# uHexV1_pub.net
KiCad netlist of a schematic drawn in EAGLE
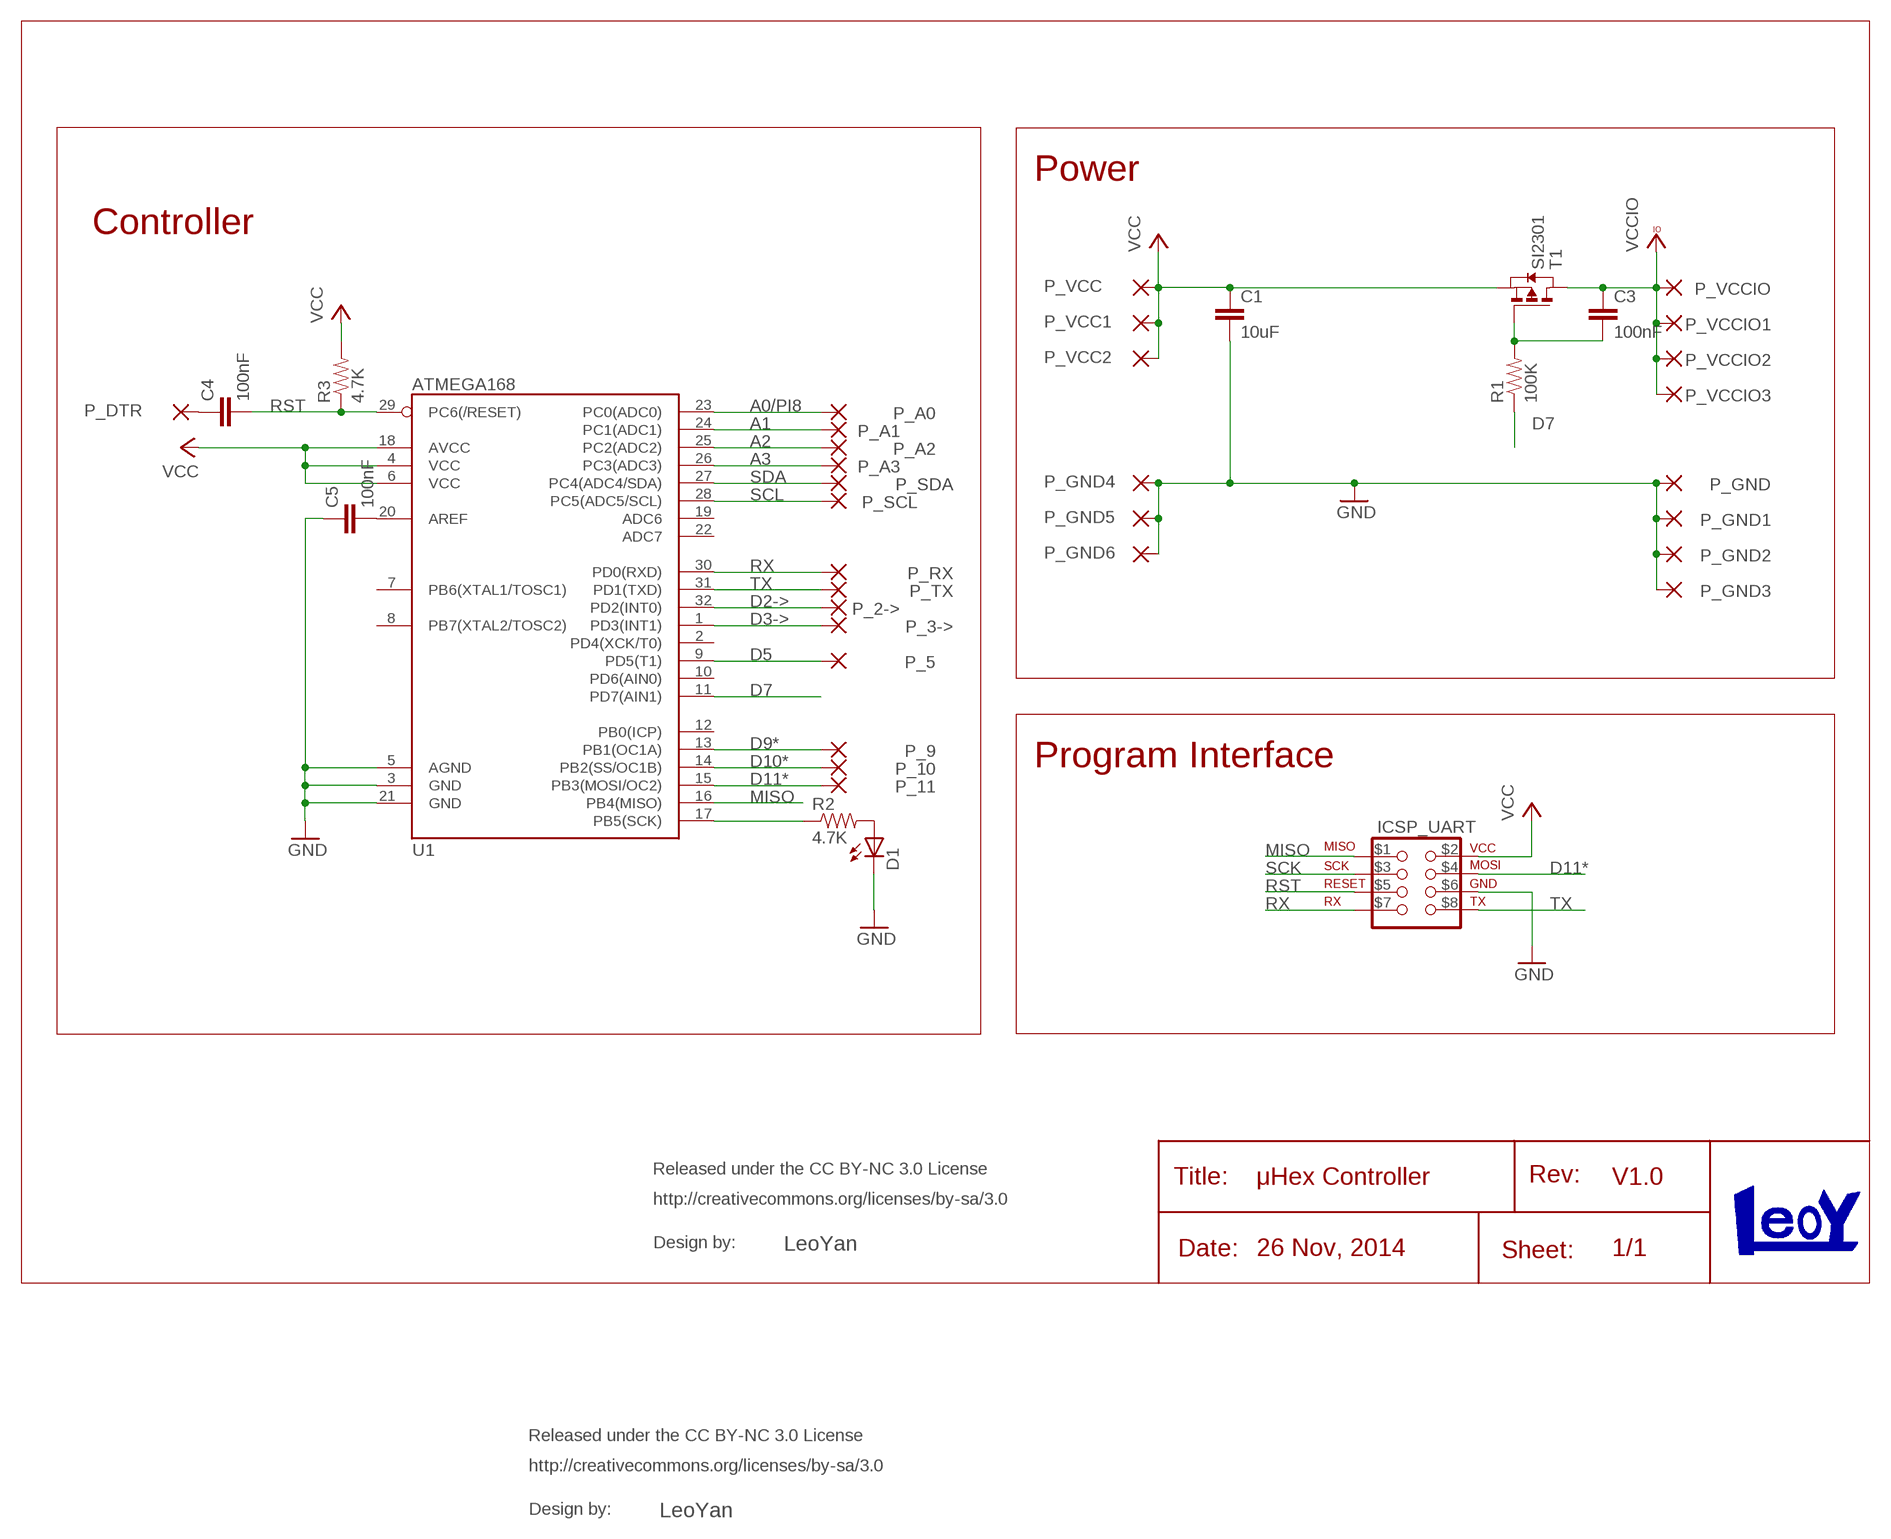
[diagram p0: schematic, sheet 1]

(export (version "E")
  (design (tool "Eeschema 10.0.6"))
  (components
    (comp (ref "C1")
      (value "10uF")
      (footprint "eagle-import:C0603K")
      (libsource (lib "eagle-import") (part "resistor_C-EUC0603K"))
    )
    (comp (ref "C3")
      (value "100nF")
      (footprint "eagle-import:C0603K")
      (libsource (lib "eagle-import") (part "C-EUC0603K"))
    )
    (comp (ref "C4")
      (value "100nF")
      (footprint "eagle-import:C0603K")
      (libsource (lib "eagle-import") (part "C-EUC0603K"))
    )
    (comp (ref "C5")
      (value "100nF")
      (footprint "eagle-import:C0603K")
      (libsource (lib "eagle-import") (part "C-EUC0603K"))
    )
    (comp (ref "D1")
      (value "LED-YELLOW0603")
      (footprint "eagle-import:LED-0603")
      (libsource (lib "eagle-import") (part "LED-YELLOW0603"))
    )
    (comp (ref "ICSP_UART")
      (value "ICSP_UART_CONNICSP_UAST_HOLE")
      (footprint "eagle-import:ICSP_UART_CONN_HOLE")
      (libsource (lib "eagle-import") (part "ICSP_UART_CONNICSP_UAST_HOLE"))
    )
    (comp (ref "P_2->")
      (value "TH-PAD2.54M01_TH_OFFSET")
      (footprint "eagle-import:TH_PAD_OFFSET")
      (libsource (lib "eagle-import") (part "TH-PAD2.54M01_TH_OFFSET"))
    )
    (comp (ref "P_3->")
      (value "TH-PAD2.54M01_TH_OFFSET")
      (footprint "eagle-import:TH_PAD_OFFSET")
      (libsource (lib "eagle-import") (part "TH-PAD2.54M01_TH_OFFSET"))
    )
    (comp (ref "P_5")
      (value "TH-PAD2.54M01_TH_HORN")
      (footprint "eagle-import:TH_PAD_HORN")
      (libsource (lib "eagle-import") (part "TH-PAD2.54M01_TH_HORN"))
    )
    (comp (ref "P_9")
      (value "TH-PAD2.54M01_TH_OFFSET")
      (footprint "eagle-import:TH_PAD_OFFSET")
      (libsource (lib "eagle-import") (part "TH-PAD2.54M01_TH_OFFSET"))
    )
    (comp (ref "P_10")
      (value "TH-PAD2.54M01_TH_OFFSET")
      (footprint "eagle-import:TH_PAD_OFFSET")
      (libsource (lib "eagle-import") (part "TH-PAD2.54M01_TH_OFFSET"))
    )
    (comp (ref "P_11")
      (value "TH-PAD2.54M01_TH_HORN")
      (footprint "eagle-import:TH_PAD_HORN")
      (libsource (lib "eagle-import") (part "TH-PAD2.54M01_TH_HORN"))
    )
    (comp (ref "P_A0")
      (value "TH-PAD2.54M01_TH_HORN")
      (footprint "eagle-import:TH_PAD_HORN")
      (libsource (lib "eagle-import") (part "TH-PAD2.54M01_TH_HORN"))
    )
    (comp (ref "P_A1")
      (value "TH-PAD2.54M01_TH_OFFSET")
      (footprint "eagle-import:TH_PAD_OFFSET")
      (libsource (lib "eagle-import") (part "TH-PAD2.54M01_TH_OFFSET"))
    )
    (comp (ref "P_A2")
      (value "TH-PAD2.54M01_TH_OFFSET")
      (footprint "eagle-import:TH_PAD_OFFSET")
      (libsource (lib "eagle-import") (part "TH-PAD2.54M01_TH_OFFSET"))
    )
    (comp (ref "P_A3")
      (value "TH-PAD2.54M01_TH_HORN")
      (footprint "eagle-import:TH_PAD_HORN")
      (libsource (lib "eagle-import") (part "TH-PAD2.54M01_TH_HORN"))
    )
    (comp (ref "P_DTR")
      (value "TH-PAD2.54MO1_TH_DTR")
      (footprint "eagle-import:TH_PAD_DTR")
      (libsource (lib "eagle-import") (part "TH-PAD2.54MO1_TH_DTR"))
    )
    (comp (ref "P_GND")
      (value "TH-PAD2.54M01_TH_PWR")
      (footprint "eagle-import:TH_PAD_PWR")
      (libsource (lib "eagle-import") (part "TH-PAD2.54M01_TH_PWR"))
    )
    (comp (ref "P_GND1")
      (value "TH-PAD2.54OFFSET")
      (footprint "eagle-import:TH_PAD_PWR_OFFSET")
      (libsource (lib "eagle-import") (part "TH-PAD2.54OFFSET"))
    )
    (comp (ref "P_GND2")
      (value "TH-PAD2.54OFFSET")
      (footprint "eagle-import:TH_PAD_PWR_OFFSET")
      (libsource (lib "eagle-import") (part "TH-PAD2.54OFFSET"))
    )
    (comp (ref "P_GND3")
      (value "TH-PAD2.54OFFSET")
      (footprint "eagle-import:TH_PAD_PWR_OFFSET")
      (libsource (lib "eagle-import") (part "TH-PAD2.54OFFSET"))
    )
    (comp (ref "P_GND4")
      (value "TH-PAD2.54OFFSET")
      (footprint "eagle-import:TH_PAD_PWR_OFFSET")
      (libsource (lib "eagle-import") (part "TH-PAD2.54OFFSET"))
    )
    (comp (ref "P_GND5")
      (value "TH-PAD2.54OFFSET")
      (footprint "eagle-import:TH_PAD_PWR_OFFSET")
      (libsource (lib "eagle-import") (part "TH-PAD2.54OFFSET"))
    )
    (comp (ref "P_GND6")
      (value "TH-PAD2.54OFFSET")
      (footprint "eagle-import:TH_PAD_PWR_OFFSET")
      (libsource (lib "eagle-import") (part "TH-PAD2.54OFFSET"))
    )
    (comp (ref "P_RX")
      (value "TH-PAD2.54M01_TH_OFFSET")
      (footprint "eagle-import:TH_PAD_OFFSET")
      (libsource (lib "eagle-import") (part "TH-PAD2.54M01_TH_OFFSET"))
    )
    (comp (ref "P_SCL")
      (value "TH-PAD2.54M01_TH_OFFSET")
      (footprint "eagle-import:TH_PAD_OFFSET")
      (libsource (lib "eagle-import") (part "TH-PAD2.54M01_TH_OFFSET"))
    )
    (comp (ref "P_SDA")
      (value "TH-PAD2.54M01_TH_OFFSET")
      (footprint "eagle-import:TH_PAD_OFFSET")
      (libsource (lib "eagle-import") (part "TH-PAD2.54M01_TH_OFFSET"))
    )
    (comp (ref "P_TX")
      (value "TH-PAD2.54M01_TH_OFFSET")
      (footprint "eagle-import:TH_PAD_OFFSET")
      (libsource (lib "eagle-import") (part "TH-PAD2.54M01_TH_OFFSET"))
    )
    (comp (ref "P_VCC")
      (value "TH-PAD2.54OFFSET")
      (footprint "eagle-import:TH_PAD_PWR_OFFSET")
      (libsource (lib "eagle-import") (part "TH-PAD2.54OFFSET"))
    )
    (comp (ref "P_VCC1")
      (value "TH-PAD2.54M01_TH_PWR")
      (footprint "eagle-import:TH_PAD_PWR")
      (libsource (lib "eagle-import") (part "TH-PAD2.54M01_TH_PWR"))
    )
    (comp (ref "P_VCC2")
      (value "TH-PAD2.54OFFSET")
      (footprint "eagle-import:TH_PAD_PWR_OFFSET")
      (libsource (lib "eagle-import") (part "TH-PAD2.54OFFSET"))
    )
    (comp (ref "P_VCCIO")
      (value "TH-PAD2.54OFFSET")
      (footprint "eagle-import:TH_PAD_PWR_OFFSET")
      (libsource (lib "eagle-import") (part "TH-PAD2.54OFFSET"))
    )
    (comp (ref "P_VCCIO1")
      (value "TH-PAD2.54OFFSET")
      (footprint "eagle-import:TH_PAD_PWR_OFFSET")
      (libsource (lib "eagle-import") (part "TH-PAD2.54OFFSET"))
    )
    (comp (ref "P_VCCIO2")
      (value "TH-PAD2.54OFFSET")
      (footprint "eagle-import:TH_PAD_PWR_OFFSET")
      (libsource (lib "eagle-import") (part "TH-PAD2.54OFFSET"))
    )
    (comp (ref "P_VCCIO3")
      (value "TH-PAD2.54OFFSET")
      (footprint "eagle-import:TH_PAD_PWR_OFFSET")
      (libsource (lib "eagle-import") (part "TH-PAD2.54OFFSET"))
    )
    (comp (ref "R1")
      (value "100K")
      (footprint "eagle-import:0603-RES")
      (libsource (lib "eagle-import") (part "RESISTOR0603-RES"))
    )
    (comp (ref "R2")
      (value "4.7K")
      (footprint "eagle-import:0603-RES")
      (libsource (lib "eagle-import") (part "RESISTOR0603-RES"))
    )
    (comp (ref "R3")
      (value "4.7K")
      (footprint "eagle-import:0603-RES")
      (libsource (lib "eagle-import") (part "RESISTOR0603-RES"))
    )
    (comp (ref "T1")
      (value "SI2301")
      (footprint "eagle-import:SOT-23")
      (libsource (lib "eagle-import") (part "PMOSSOT23"))
    )
    (comp (ref "U1")
      (value "ATMEGA168")
      (footprint "eagle-import:TQFP32-08")
      (libsource (lib "eagle-import") (part "ATMEGA168"))
    )
  )
  (nets
    (net (code "1") (name "/A0{slash}PI8") (class "Default")
      (node (ref "P_A0") (pin "1") (pinfunction "P$_1") (pintype "bidirectional"))
      (node (ref "U1") (pin "23") (pinfunction "PC0(ADC0)_23") (pintype "bidirectional"))
    )
    (net (code "2") (name "/A1") (class "Default")
      (node (ref "P_A1") (pin "P$1") (pinfunction "P$_P$1") (pintype "bidirectional"))
      (node (ref "U1") (pin "24") (pinfunction "PC1(ADC1)_24") (pintype "bidirectional"))
    )
    (net (code "3") (name "/A2") (class "Default")
      (node (ref "P_A2") (pin "P$1") (pinfunction "P$_P$1") (pintype "bidirectional"))
      (node (ref "U1") (pin "25") (pinfunction "PC2(ADC2)_25") (pintype "bidirectional"))
    )
    (net (code "4") (name "/A3") (class "Default")
      (node (ref "P_A3") (pin "1") (pinfunction "P$_1") (pintype "bidirectional"))
      (node (ref "U1") (pin "26") (pinfunction "PC3(ADC3)_26") (pintype "bidirectional"))
    )
    (net (code "5") (name "/D2->") (class "Default")
      (node (ref "P_2->") (pin "P$1") (pinfunction "P$_P$1") (pintype "bidirectional"))
      (node (ref "U1") (pin "32") (pinfunction "PD2(INT0)_32") (pintype "bidirectional"))
    )
    (net (code "6") (name "/D3->") (class "Default")
      (node (ref "P_3->") (pin "P$1") (pinfunction "P$_P$1") (pintype "bidirectional"))
      (node (ref "U1") (pin "1") (pinfunction "PD3(INT1)_1") (pintype "bidirectional"))
    )
    (net (code "7") (name "/D5") (class "Default")
      (node (ref "P_5") (pin "1") (pinfunction "P$_1") (pintype "bidirectional"))
      (node (ref "U1") (pin "9") (pinfunction "PD5(T1)_9") (pintype "bidirectional"))
    )
    (net (code "8") (name "/D7") (class "Default")
      (node (ref "R1") (pin "1") (pinfunction "1_1") (pintype "passive"))
      (node (ref "U1") (pin "11") (pinfunction "PD7(AIN1)_11") (pintype "bidirectional"))
    )
    (net (code "9") (name "/D9*") (class "Default")
      (node (ref "P_9") (pin "P$1") (pinfunction "P$_P$1") (pintype "bidirectional"))
      (node (ref "U1") (pin "13") (pinfunction "PB1(OC1A)_13") (pintype "bidirectional"))
    )
    (net (code "10") (name "/D10*") (class "Default")
      (node (ref "P_10") (pin "P$1") (pinfunction "P$_P$1") (pintype "bidirectional"))
      (node (ref "U1") (pin "14") (pinfunction "PB2(SS/OC1B)_14") (pintype "bidirectional"))
    )
    (net (code "11") (name "/D11*") (class "Default")
      (node (ref "ICSP_UART") (pin "$4") (pinfunction "4_$4") (pintype "passive"))
      (node (ref "P_11") (pin "1") (pinfunction "P$_1") (pintype "bidirectional"))
      (node (ref "U1") (pin "15") (pinfunction "PB3(MOSI/OC2)_15") (pintype "bidirectional"))
    )
    (net (code "12") (name "/MISO") (class "Default")
      (node (ref "ICSP_UART") (pin "$1") (pinfunction "1_$1") (pintype "output"))
      (node (ref "U1") (pin "16") (pinfunction "PB4(MISO)_16") (pintype "bidirectional"))
    )
    (net (code "13") (name "/RST") (class "Default")
      (node (ref "C4") (pin "2") (pinfunction "2_2") (pintype "passive"))
      (node (ref "ICSP_UART") (pin "$5") (pinfunction "5_$5") (pintype "passive"))
      (node (ref "R3") (pin "1") (pinfunction "1_1") (pintype "passive"))
      (node (ref "U1") (pin "29") (pinfunction "PC6(/RESET)_29") (pintype "bidirectional"))
    )
    (net (code "14") (name "/RX") (class "Default")
      (node (ref "ICSP_UART") (pin "$7") (pinfunction "7_$7") (pintype "passive"))
      (node (ref "P_RX") (pin "P$1") (pinfunction "P$_P$1") (pintype "bidirectional"))
      (node (ref "U1") (pin "30") (pinfunction "PD0(RXD)_30") (pintype "bidirectional"))
    )
    (net (code "15") (name "/SCK") (class "Default")
      (node (ref "ICSP_UART") (pin "$3") (pinfunction "3_$3") (pintype "passive"))
      (node (ref "R2") (pin "1") (pinfunction "1_1") (pintype "passive"))
      (node (ref "U1") (pin "17") (pinfunction "PB5(SCK)_17") (pintype "bidirectional"))
    )
    (net (code "16") (name "/SCL") (class "Default")
      (node (ref "P_SCL") (pin "P$1") (pinfunction "P$_P$1") (pintype "bidirectional"))
      (node (ref "U1") (pin "28") (pinfunction "PC5(ADC5/SCL)_28") (pintype "bidirectional"))
    )
    (net (code "17") (name "/SDA") (class "Default")
      (node (ref "P_SDA") (pin "P$1") (pinfunction "P$_P$1") (pintype "bidirectional"))
      (node (ref "U1") (pin "27") (pinfunction "PC4(ADC4/SDA)_27") (pintype "bidirectional"))
    )
    (net (code "18") (name "/TX") (class "Default")
      (node (ref "ICSP_UART") (pin "$8") (pinfunction "8_$8") (pintype "passive"))
      (node (ref "P_TX") (pin "P$1") (pinfunction "P$_P$1") (pintype "bidirectional"))
      (node (ref "U1") (pin "31") (pinfunction "PD1(TXD)_31") (pintype "bidirectional"))
    )
    (net (code "19") (name "GND") (class "Default")
      (node (ref "C1") (pin "2") (pinfunction "2_2") (pintype "passive"))
      (node (ref "C5") (pin "1") (pinfunction "1_1") (pintype "passive"))
      (node (ref "D1") (pin "C") (pinfunction "C_C") (pintype "passive"))
      (node (ref "ICSP_UART") (pin "$6") (pinfunction "6_$6") (pintype "passive"))
      (node (ref "P_GND") (pin "P$1") (pinfunction "P$_P$1") (pintype "bidirectional"))
      (node (ref "P_GND1") (pin "P$1") (pinfunction "P$_P$1") (pintype "bidirectional"))
      (node (ref "P_GND2") (pin "P$1") (pinfunction "P$_P$1") (pintype "bidirectional"))
      (node (ref "P_GND3") (pin "P$1") (pinfunction "P$_P$1") (pintype "bidirectional"))
      (node (ref "P_GND4") (pin "P$1") (pinfunction "P$_P$1") (pintype "bidirectional"))
      (node (ref "P_GND5") (pin "P$1") (pinfunction "P$_P$1") (pintype "bidirectional"))
      (node (ref "P_GND6") (pin "P$1") (pinfunction "P$_P$1") (pintype "bidirectional"))
      (node (ref "U1") (pin "21") (pinfunction "GND_21") (pintype "bidirectional"))
      (node (ref "U1") (pin "3") (pinfunction "GND_3") (pintype "bidirectional"))
      (node (ref "U1") (pin "5") (pinfunction "AGND_5") (pintype "bidirectional"))
    )
    (net (code "20") (name "Net-(D1-PadA)") (class "Default")
      (node (ref "D1") (pin "A") (pinfunction "A_A") (pintype "passive"))
      (node (ref "R2") (pin "2") (pinfunction "2_2") (pintype "passive"))
    )
    (net (code "21") (name "Net-(P_DTR-P$)") (class "Default")
      (node (ref "C4") (pin "1") (pinfunction "1_1") (pintype "passive"))
      (node (ref "P_DTR") (pin "1") (pinfunction "P$_1") (pintype "bidirectional"))
    )
    (net (code "22") (name "Net-(T1-G)") (class "Default")
      (node (ref "C3") (pin "2") (pinfunction "2_2") (pintype "passive"))
      (node (ref "R1") (pin "2") (pinfunction "2_2") (pintype "passive"))
      (node (ref "T1") (pin "3") (pinfunction "G_3") (pintype "passive"))
    )
    (net (code "23") (name "Net-(U1-AREF)") (class "Default")
      (node (ref "C5") (pin "2") (pinfunction "2_2") (pintype "passive"))
      (node (ref "U1") (pin "20") (pinfunction "AREF_20") (pintype "bidirectional"))
    )
    (net (code "24") (name "VCC") (class "Default")
      (node (ref "C1") (pin "1") (pinfunction "1_1") (pintype "passive"))
      (node (ref "ICSP_UART") (pin "$2") (pinfunction "2_$2") (pintype "power_in"))
      (node (ref "P_VCC") (pin "P$1") (pinfunction "P$_P$1") (pintype "bidirectional"))
      (node (ref "P_VCC1") (pin "P$1") (pinfunction "P$_P$1") (pintype "bidirectional"))
      (node (ref "P_VCC2") (pin "P$1") (pinfunction "P$_P$1") (pintype "bidirectional"))
      (node (ref "R3") (pin "2") (pinfunction "2_2") (pintype "passive"))
      (node (ref "T1") (pin "2") (pinfunction "S_2") (pintype "passive"))
      (node (ref "U1") (pin "18") (pinfunction "AVCC_18") (pintype "bidirectional"))
      (node (ref "U1") (pin "4") (pinfunction "VCC_4") (pintype "bidirectional"))
      (node (ref "U1") (pin "6") (pinfunction "VCC_6") (pintype "bidirectional"))
    )
    (net (code "25") (name "VCCIO") (class "Default")
      (node (ref "C3") (pin "1") (pinfunction "1_1") (pintype "passive"))
      (node (ref "P_VCCIO") (pin "P$1") (pinfunction "P$_P$1") (pintype "bidirectional"))
      (node (ref "P_VCCIO1") (pin "P$1") (pinfunction "P$_P$1") (pintype "bidirectional"))
      (node (ref "P_VCCIO2") (pin "P$1") (pinfunction "P$_P$1") (pintype "bidirectional"))
      (node (ref "P_VCCIO3") (pin "P$1") (pinfunction "P$_P$1") (pintype "bidirectional"))
      (node (ref "T1") (pin "1") (pinfunction "D_1") (pintype "passive"))
    )
    (net (code "26") (name "unconnected-(U1-ADC6-Pad19)") (class "Default")
      (node (ref "U1") (pin "19") (pinfunction "ADC6_19") (pintype "bidirectional"))
    )
    (net (code "27") (name "unconnected-(U1-ADC7-Pad22)") (class "Default")
      (node (ref "U1") (pin "22") (pinfunction "ADC7_22") (pintype "bidirectional"))
    )
    (net (code "28") (name "unconnected-(U1-PB0(ICP)-Pad12)") (class "Default")
      (node (ref "U1") (pin "12") (pinfunction "PB0(ICP)_12") (pintype "bidirectional"))
    )
    (net (code "29") (name "unconnected-(U1-PB6(XTAL1{slash}TOSC1)-Pad7)") (class "Default")
      (node (ref "U1") (pin "7") (pinfunction "PB6(XTAL1/TOSC1)_7") (pintype "bidirectional"))
    )
    (net (code "30") (name "unconnected-(U1-PB7(XTAL2{slash}TOSC2)-Pad8)") (class "Default")
      (node (ref "U1") (pin "8") (pinfunction "PB7(XTAL2/TOSC2)_8") (pintype "bidirectional"))
    )
    (net (code "31") (name "unconnected-(U1-PD4(XCK{slash}T0)-Pad2)") (class "Default")
      (node (ref "U1") (pin "2") (pinfunction "PD4(XCK/T0)_2") (pintype "bidirectional"))
    )
    (net (code "32") (name "unconnected-(U1-PD6(AIN0)-Pad10)") (class "Default")
      (node (ref "U1") (pin "10") (pinfunction "PD6(AIN0)_10") (pintype "bidirectional"))
    )
  )
)
